# RCMX_Rev_00_BPS_NewSilk.net
KiCad netlist of a schematic drawn in EAGLE
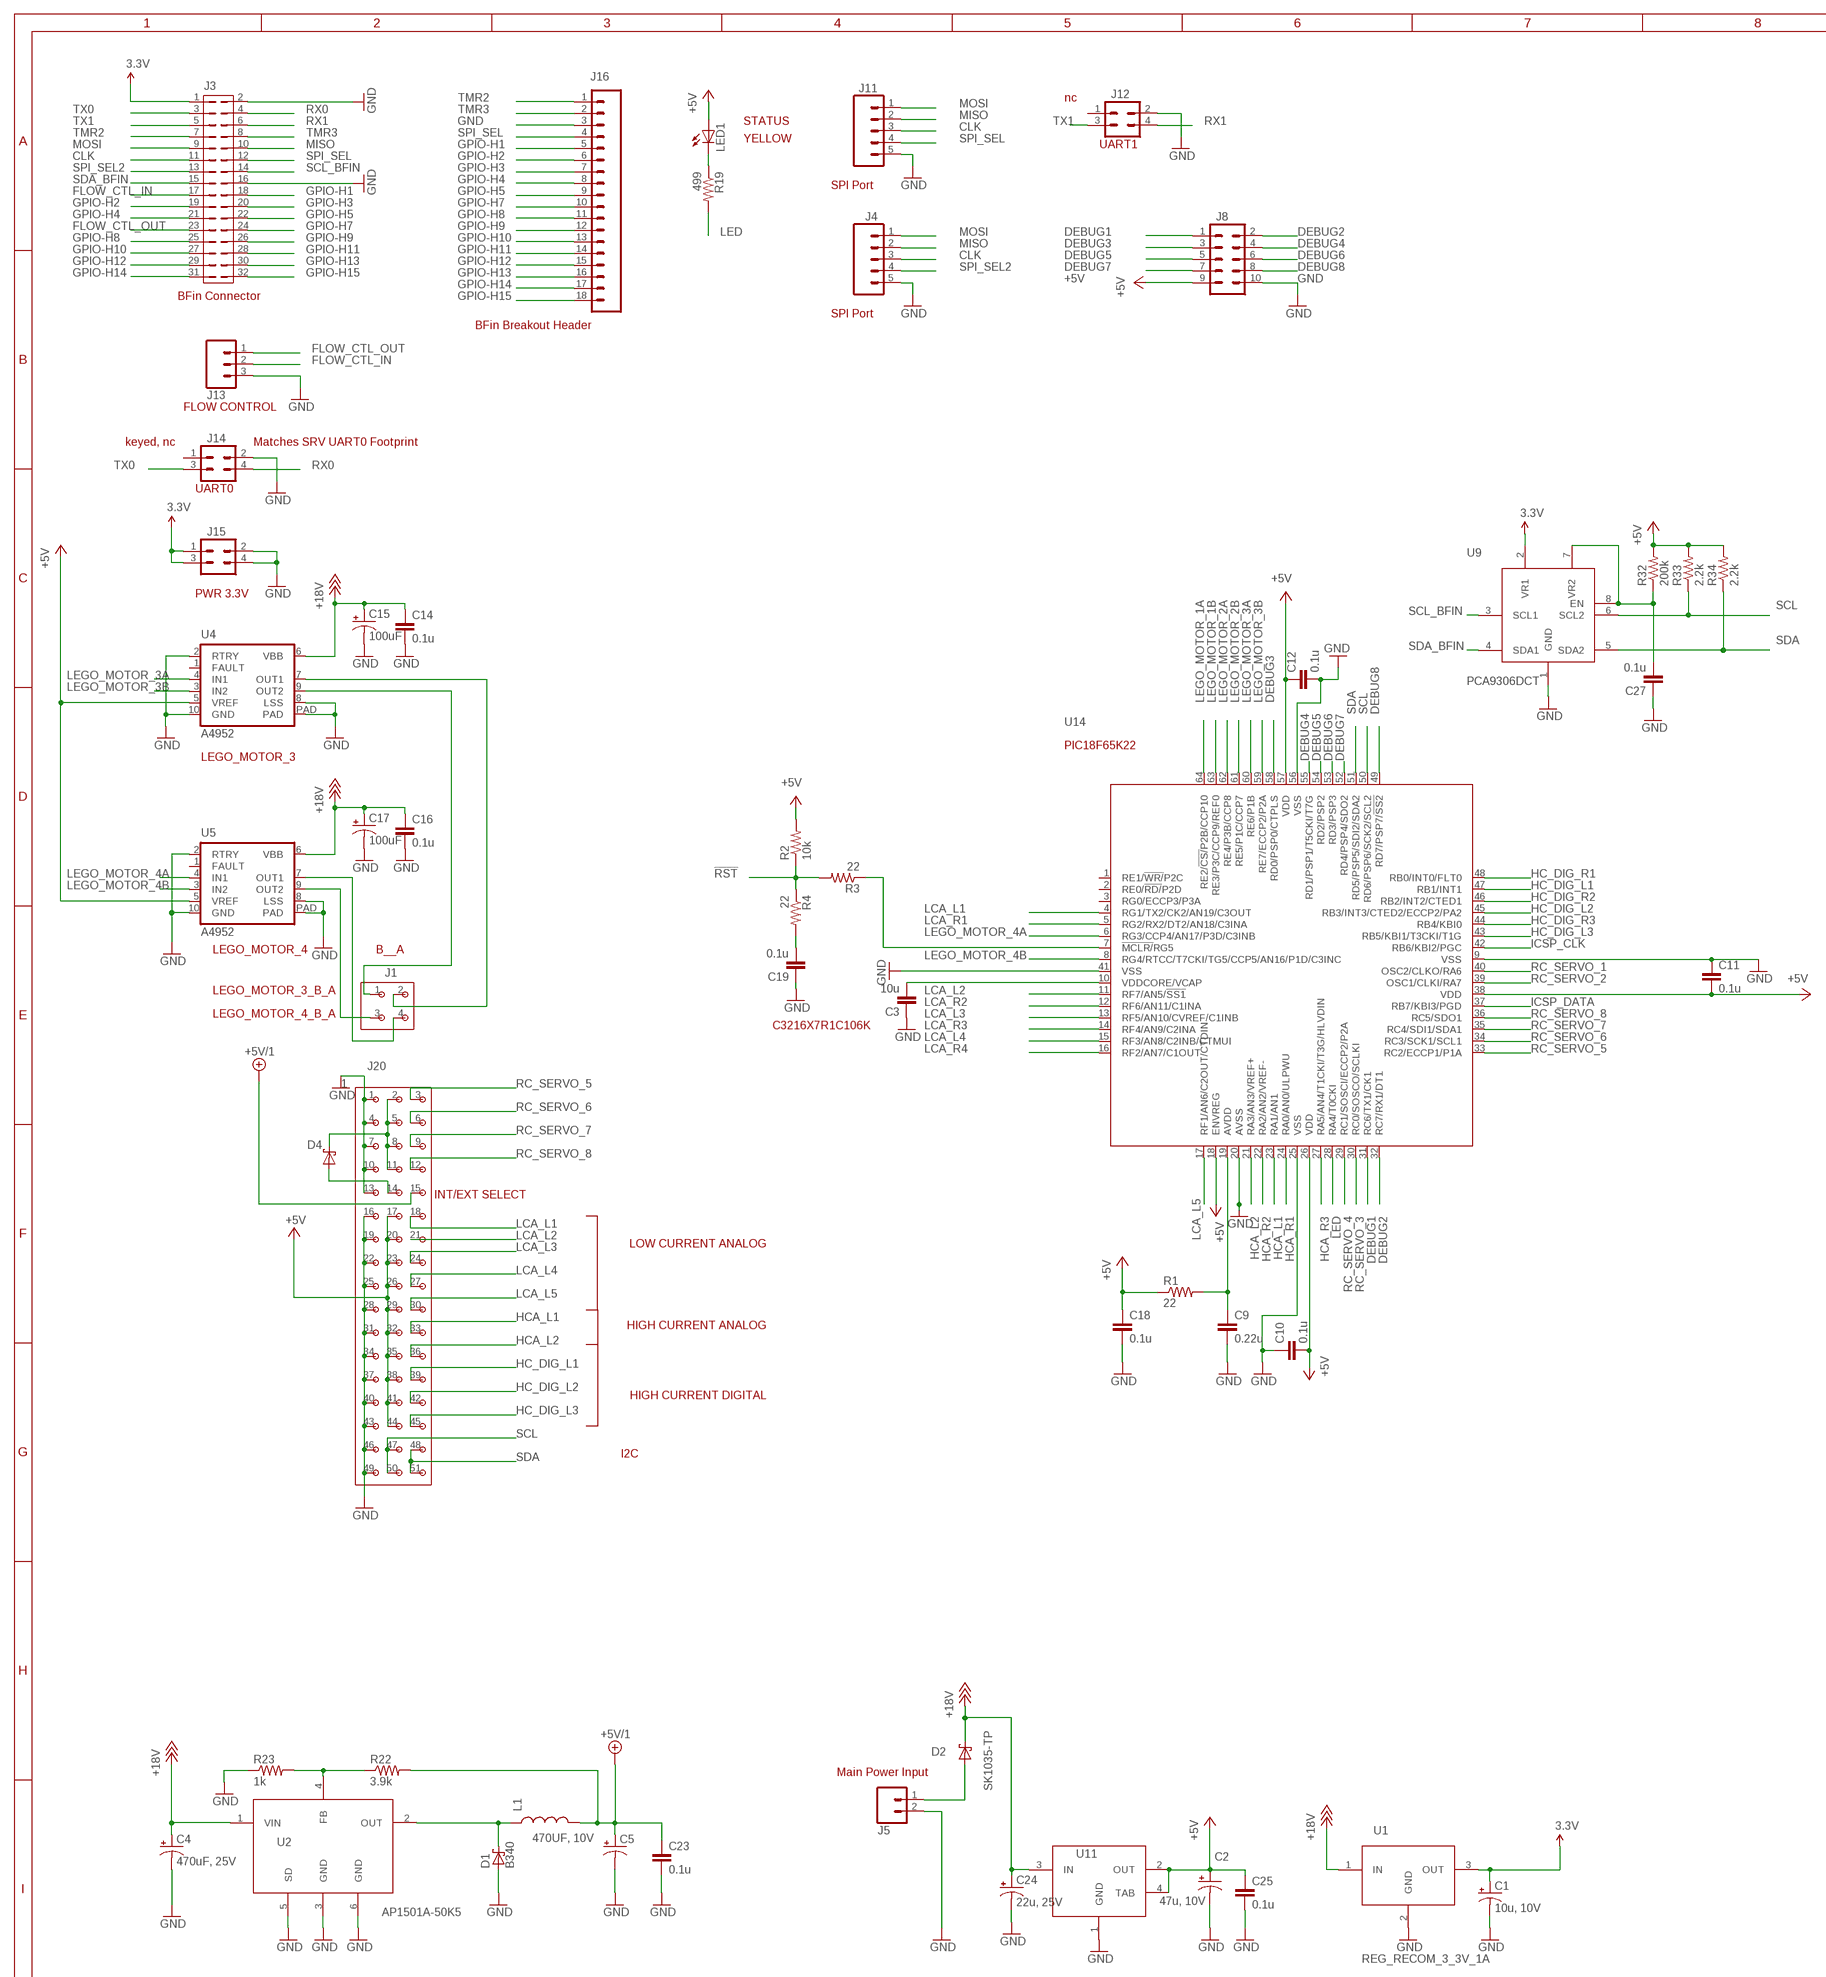
[diagram p0: schematic, sheet 1, part 1 of 2]
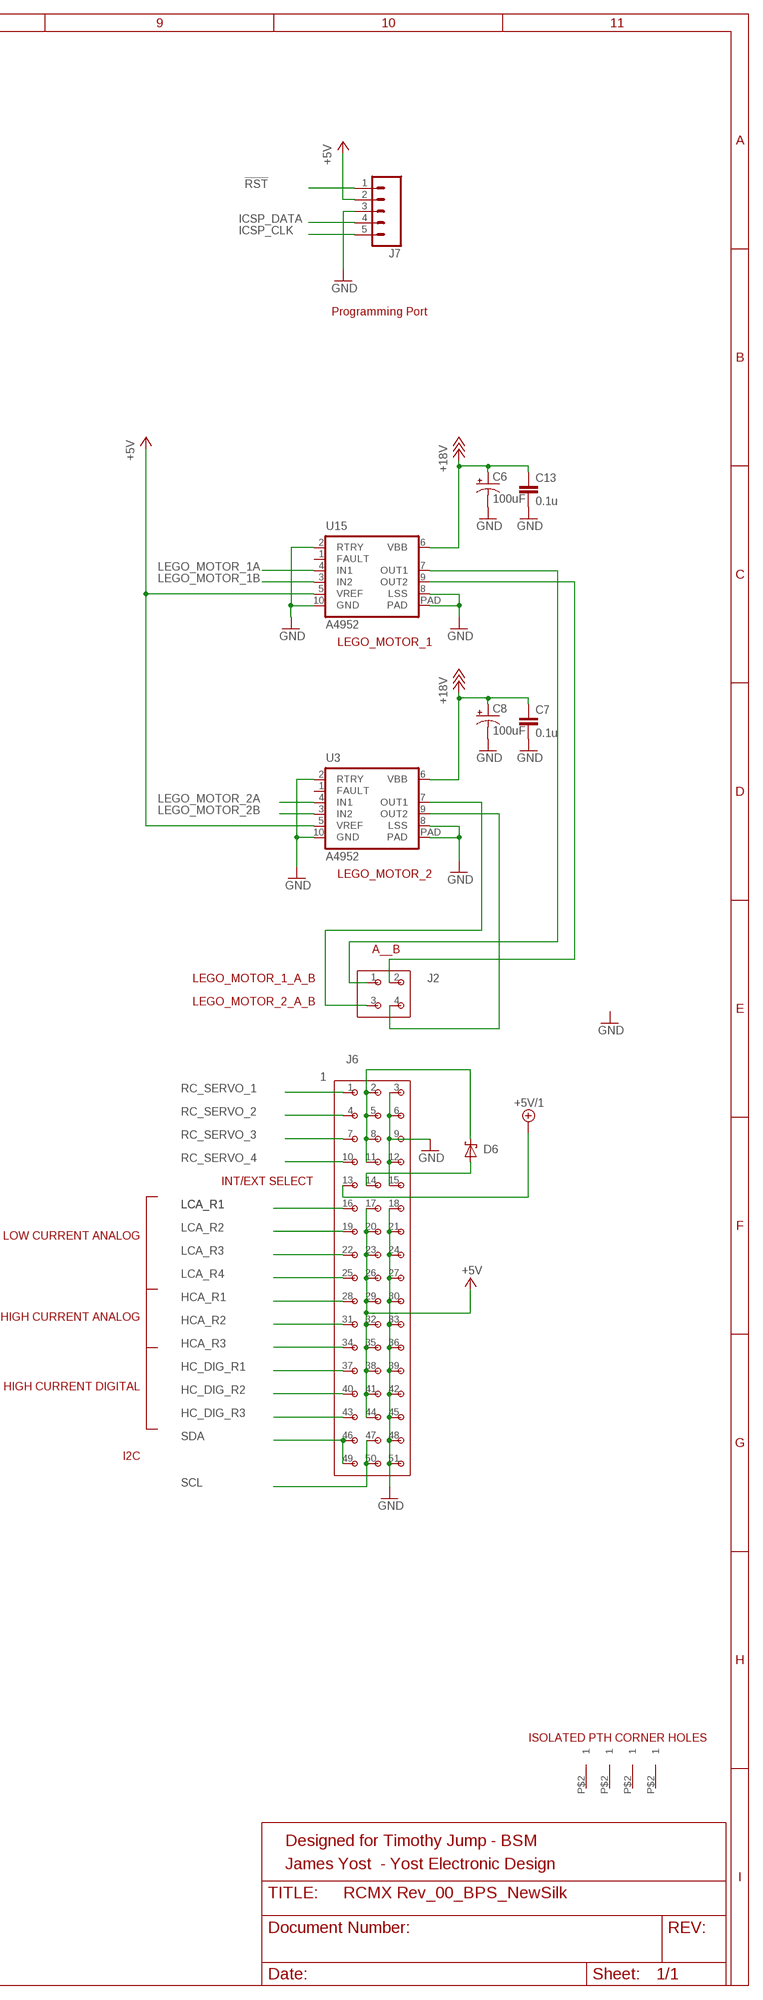
[diagram p1: schematic, sheet 1, part 2 of 2]

(export (version "E")
  (design (tool "Eeschema 10.0.6"))
  (components
    (comp (ref "C1")
      (value "10u, 10V")
      (footprint "eagle-import:EIA3216")
      (libsource (lib "eagle-import") (part "CAP_POL1206"))
    )
    (comp (ref "C2")
      (value "47u, 10V")
      (footprint "eagle-import:CAP1210_POL")
      (libsource (lib "eagle-import") (part "CAP_1210_POL"))
    )
    (comp (ref "C3")
      (value "10u")
      (footprint "eagle-import:1206")
      (libsource (lib "eagle-import") (part "CAP1206"))
    )
    (comp (ref "C4")
      (value "470uF, 25V")
      (footprint "eagle-import:PANASONIC_G")
      (libsource (lib "eagle-import") (part "CAP_POLG"))
    )
    (comp (ref "C5")
      (value "470UF, 10V")
      (footprint "eagle-import:PANASONIC_F")
      (libsource (lib "eagle-import") (part "CAP_ELT_PANASONIC_470UF"))
    )
    (comp (ref "C6")
      (value "100uF")
      (footprint "eagle-import:PANASONIC_D")
      (libsource (lib "eagle-import") (part "CAP_POLD"))
    )
    (comp (ref "C7")
      (value "0.1u")
      (footprint "eagle-import:0805")
      (libsource (lib "eagle-import") (part "CAP0805"))
    )
    (comp (ref "C8")
      (value "100uF")
      (footprint "eagle-import:PANASONIC_D")
      (libsource (lib "eagle-import") (part "CAP_POLD"))
    )
    (comp (ref "C9")
      (value "0.22u")
      (footprint "eagle-import:0805")
      (libsource (lib "eagle-import") (part "CAP0805"))
    )
    (comp (ref "C10")
      (value "0.1u")
      (footprint "eagle-import:0805")
      (libsource (lib "eagle-import") (part "CAP0805"))
    )
    (comp (ref "C11")
      (value "0.1u")
      (footprint "eagle-import:0805")
      (libsource (lib "eagle-import") (part "CAP0805"))
    )
    (comp (ref "C12")
      (value "0.1u")
      (footprint "eagle-import:0805")
      (libsource (lib "eagle-import") (part "CAP0805"))
    )
    (comp (ref "C13")
      (value "0.1u")
      (footprint "eagle-import:0805")
      (libsource (lib "eagle-import") (part "CAP0805"))
    )
    (comp (ref "C14")
      (value "0.1u")
      (footprint "eagle-import:0805")
      (libsource (lib "eagle-import") (part "CAP0805"))
    )
    (comp (ref "C15")
      (value "100uF")
      (footprint "eagle-import:PANASONIC_D")
      (libsource (lib "eagle-import") (part "CAP_POLD"))
    )
    (comp (ref "C16")
      (value "0.1u")
      (footprint "eagle-import:0805")
      (libsource (lib "eagle-import") (part "CAP0805"))
    )
    (comp (ref "C17")
      (value "100uF")
      (footprint "eagle-import:PANASONIC_D")
      (libsource (lib "eagle-import") (part "CAP_POLD"))
    )
    (comp (ref "C18")
      (value "0.1u")
      (footprint "eagle-import:0805")
      (libsource (lib "eagle-import") (part "CAP0805"))
    )
    (comp (ref "C19")
      (value "0.1u")
      (footprint "eagle-import:0805")
      (libsource (lib "eagle-import") (part "CAP0805"))
    )
    (comp (ref "C23")
      (value "0.1u")
      (footprint "eagle-import:0805")
      (libsource (lib "eagle-import") (part "CAP0805"))
    )
    (comp (ref "C24")
      (value "22u, 25V")
      (footprint "eagle-import:CAP1210_POL")
      (libsource (lib "eagle-import") (part "CAP_1210_POL"))
    )
    (comp (ref "C25")
      (value "0.1u")
      (footprint "eagle-import:0805")
      (libsource (lib "eagle-import") (part "CAP0805"))
    )
    (comp (ref "C27")
      (value "0.1u")
      (footprint "eagle-import:0805")
      (libsource (lib "eagle-import") (part "CAP0805"))
    )
    (comp (ref "D1")
      (value "B340")
      (footprint "eagle-import:SMA_DO214AC")
      (libsource (lib "eagle-import") (part "B340"))
    )
    (comp (ref "D2")
      (value "SK1035-TP")
      (footprint "eagle-import:DO214AB")
      (libsource (lib "eagle-import") (part "SK1035-TP"))
    )
    (comp (ref "D4")
      (value "SK1035-TP")
      (footprint "eagle-import:DO214AB")
      (libsource (lib "eagle-import") (part "SK1035-TP"))
    )
    (comp (ref "D6")
      (value "SK1035-TP")
      (footprint "eagle-import:DO214AB")
      (libsource (lib "eagle-import") (part "SK1035-TP"))
    )
    (comp (ref "J1")
      (value "CON_2X2_0_100")
      (footprint "eagle-import:CON_2X2_0_100")
      (libsource (lib "eagle-import") (part "CON_2X2_0_100"))
    )
    (comp (ref "J2")
      (value "CON_2X2_0_100")
      (footprint "eagle-import:CON_2X2_0_100")
      (libsource (lib "eagle-import") (part "CON_2X2_0_100"))
    )
    (comp (ref "J3")
      (value "CON_2X16_0_100")
      (footprint "eagle-import:CON_2X16_0_100")
      (libsource (lib "eagle-import") (part "CON_2X16_0_100"))
    )
    (comp (ref "J4")
      (value "M05PTH")
      (footprint "eagle-import:1X05")
      (libsource (lib "eagle-import") (part "M05PTH"))
    )
    (comp (ref "J5")
      (value "M02NG")
      (footprint "eagle-import:1X02")
      (libsource (lib "eagle-import") (part "M02NG"))
    )
    (comp (ref "J6")
      (value "CON_3X17_0_100")
      (footprint "eagle-import:CON_3X17_0_100")
      (libsource (lib "eagle-import") (part "CON_3X17_0_100"))
    )
    (comp (ref "J7")
      (value "M05PTH")
      (footprint "eagle-import:1X05")
      (libsource (lib "eagle-import") (part "SparkFun-Connectors_M05PTH"))
    )
    (comp (ref "J8")
      (value "M05X2PTH")
      (footprint "eagle-import:AVR_ICSP")
      (libsource (lib "eagle-import") (part "M05X2PTH"))
    )
    (comp (ref "J11")
      (value "M05PTH")
      (footprint "eagle-import:1X05")
      (libsource (lib "eagle-import") (part "M05PTH"))
    )
    (comp (ref "J12")
      (value "CON2X2")
      (footprint "eagle-import:CON2X2")
      (libsource (lib "eagle-import") (part "CON2X2"))
    )
    (comp (ref "J13")
      (value "M03PTH")
      (footprint "eagle-import:1X03")
      (libsource (lib "eagle-import") (part "M03PTH"))
    )
    (comp (ref "J14")
      (value "CON2X2")
      (footprint "eagle-import:CON2X2")
      (libsource (lib "eagle-import") (part "CON2X2"))
    )
    (comp (ref "J15")
      (value "CON2X2")
      (footprint "eagle-import:CON2X2")
      (libsource (lib "eagle-import") (part "CON2X2"))
    )
    (comp (ref "J16")
      (value "CON1X18")
      (footprint "eagle-import:CON1X18")
      (libsource (lib "eagle-import") (part "CON1X18"))
    )
    (comp (ref "J20")
      (value "CON_3X17_0_100")
      (footprint "eagle-import:CON_3X17_0_100")
      (libsource (lib "eagle-import") (part "CON_3X17_0_100"))
    )
    (comp (ref "L1")
      (value "IND_47UH_COILTRONICS_2_95A")
      (footprint "eagle-import:IND_PADS_SMT")
      (libsource (lib "eagle-import") (part "IND_47UH_COILTRONICS_2_95A"))
    )
    (comp (ref "LED1")
      (value "LEDCHIP-LED0805")
      (footprint "eagle-import:CHIP-LED0805")
      (libsource (lib "eagle-import") (part "LEDCHIP-LED0805"))
    )
    (comp (ref "R1")
      (value "22")
      (footprint "eagle-import:0805")
      (libsource (lib "eagle-import") (part "RESISTOR"))
    )
    (comp (ref "R2")
      (value "10k")
      (footprint "eagle-import:0805")
      (libsource (lib "eagle-import") (part "RESISTOR"))
    )
    (comp (ref "R3")
      (value "22")
      (footprint "eagle-import:0805")
      (libsource (lib "eagle-import") (part "RESISTOR"))
    )
    (comp (ref "R4")
      (value "22")
      (footprint "eagle-import:0805")
      (libsource (lib "eagle-import") (part "RESISTOR"))
    )
    (comp (ref "R19")
      (value "499")
      (footprint "eagle-import:0805")
      (libsource (lib "eagle-import") (part "RESISTOR"))
    )
    (comp (ref "R22")
      (value "3.9k")
      (footprint "eagle-import:0805")
      (libsource (lib "eagle-import") (part "RESISTOR"))
    )
    (comp (ref "R23")
      (value "1k")
      (footprint "eagle-import:0805")
      (libsource (lib "eagle-import") (part "RESISTOR"))
    )
    (comp (ref "R32")
      (value "200k")
      (footprint "eagle-import:0805")
      (libsource (lib "eagle-import") (part "RESISTOR"))
    )
    (comp (ref "R33")
      (value "2.2k")
      (footprint "eagle-import:0805")
      (libsource (lib "eagle-import") (part "RESISTOR"))
    )
    (comp (ref "R34")
      (value "2.2k")
      (footprint "eagle-import:0805")
      (libsource (lib "eagle-import") (part "RESISTOR"))
    )
    (comp (ref "U$1")
      (value "GNDPAD")
      (footprint "eagle-import:GNDPAD")
      (libsource (lib "eagle-import") (part "GNDPAD"))
    )
    (comp (ref "U$2")
      (value "GNDPAD")
      (footprint "eagle-import:GNDPAD")
      (libsource (lib "eagle-import") (part "GNDPAD"))
    )
    (comp (ref "U$7")
      (value "GNDPAD")
      (footprint "eagle-import:GNDPAD")
      (libsource (lib "eagle-import") (part "GNDPAD"))
    )
    (comp (ref "U$8")
      (value "GNDPAD")
      (footprint "eagle-import:GNDPAD")
      (libsource (lib "eagle-import") (part "GNDPAD"))
    )
    (comp (ref "U1")
      (value "REG_RECOM_3_3V_1A")
      (footprint "eagle-import:REG_RECOM_3_3V_1A")
      (libsource (lib "eagle-import") (part "REG_RECOM_3_3V_1A"))
    )
    (comp (ref "U2")
      (value "AP1501A-50K5")
      (footprint "eagle-import:TO263-5")
      (libsource (lib "eagle-import") (part "AP1501A-50K5"))
    )
    (comp (ref "U3")
      (value "A4952")
      (footprint "eagle-import:MSOP10_W_THERMAL_PAD")
      (libsource (lib "eagle-import") (part "A4952"))
    )
    (comp (ref "U4")
      (value "A4952")
      (footprint "eagle-import:MSOP10_W_THERMAL_PAD")
      (libsource (lib "eagle-import") (part "A4952"))
    )
    (comp (ref "U5")
      (value "A4952")
      (footprint "eagle-import:MSOP10_W_THERMAL_PAD")
      (libsource (lib "eagle-import") (part "A4952"))
    )
    (comp (ref "U9")
      (value "PCA9306DCT")
      (footprint "eagle-import:TEST08")
      (libsource (lib "eagle-import") (part "PCA9306DCT"))
    )
    (comp (ref "U11")
      (value "TLV1117-5")
      (footprint "eagle-import:SOT223")
      (libsource (lib "eagle-import") (part "TLV1117-5"))
    )
    (comp (ref "U14")
      (value "MICRO_C_PIC18F65K22")
      (footprint "eagle-import:64PIN_TQFP_10X10X1MM")
      (libsource (lib "eagle-import") (part "MICRO_C_PIC18F65K22"))
    )
    (comp (ref "U15")
      (value "A4952")
      (footprint "eagle-import:MSOP10_W_THERMAL_PAD")
      (libsource (lib "eagle-import") (part "A4952"))
    )
  )
  (nets
    (net (code "1") (name "+5V") (class "Default")
      (node (ref "C10") (pin "2") (pinfunction "2_2") (pintype "passive"))
      (node (ref "C11") (pin "2") (pinfunction "2_2") (pintype "passive"))
      (node (ref "C12") (pin "1") (pinfunction "1_1") (pintype "passive"))
      (node (ref "C18") (pin "1") (pinfunction "1_1") (pintype "passive"))
      (node (ref "C2") (pin "1") (pinfunction "+_1") (pintype "passive"))
      (node (ref "C25") (pin "1") (pinfunction "1_1") (pintype "passive"))
      (node (ref "J20") (pin "17") (pinfunction "17_17") (pintype "passive"))
      (node (ref "J20") (pin "20") (pinfunction "20_20") (pintype "passive"))
      (node (ref "J20") (pin "23") (pinfunction "23_23") (pintype "passive"))
      (node (ref "J20") (pin "26") (pinfunction "26_26") (pintype "passive"))
      (node (ref "J20") (pin "29") (pinfunction "29_29") (pintype "passive"))
      (node (ref "J20") (pin "32") (pinfunction "32_32") (pintype "passive"))
      (node (ref "J20") (pin "35") (pinfunction "35_35") (pintype "passive"))
      (node (ref "J20") (pin "38") (pinfunction "38_38") (pintype "passive"))
      (node (ref "J20") (pin "41") (pinfunction "41_41") (pintype "passive"))
      (node (ref "J20") (pin "44") (pinfunction "44_44") (pintype "passive"))
      (node (ref "J6") (pin "17") (pinfunction "17_17") (pintype "passive"))
      (node (ref "J6") (pin "20") (pinfunction "20_20") (pintype "passive"))
      (node (ref "J6") (pin "23") (pinfunction "23_23") (pintype "passive"))
      (node (ref "J6") (pin "26") (pinfunction "26_26") (pintype "passive"))
      (node (ref "J6") (pin "29") (pinfunction "29_29") (pintype "passive"))
      (node (ref "J6") (pin "32") (pinfunction "32_32") (pintype "passive"))
      (node (ref "J6") (pin "35") (pinfunction "35_35") (pintype "passive"))
      (node (ref "J6") (pin "38") (pinfunction "38_38") (pintype "passive"))
      (node (ref "J6") (pin "41") (pinfunction "41_41") (pintype "passive"))
      (node (ref "J6") (pin "44") (pinfunction "44_44") (pintype "passive"))
      (node (ref "J7") (pin "2") (pinfunction "2_2") (pintype "passive"))
      (node (ref "J8") (pin "9") (pinfunction "9_9") (pintype "passive"))
      (node (ref "LED1") (pin "A") (pinfunction "A_A") (pintype "passive"))
      (node (ref "R1") (pin "1") (pinfunction "1_1") (pintype "passive"))
      (node (ref "R2") (pin "2") (pinfunction "2_2") (pintype "passive"))
      (node (ref "R32") (pin "2") (pinfunction "2_2") (pintype "passive"))
      (node (ref "R33") (pin "2") (pinfunction "2_2") (pintype "passive"))
      (node (ref "R34") (pin "2") (pinfunction "2_2") (pintype "passive"))
      (node (ref "U11") (pin "2") (pinfunction "OUT_2") (pintype "bidirectional"))
      (node (ref "U11") (pin "4") (pinfunction "TAB_4") (pintype "bidirectional"))
      (node (ref "U14") (pin "18") (pinfunction "ENVREG_18") (pintype "input"))
      (node (ref "U14") (pin "26") (pinfunction "VDD_26") (pintype "power_in"))
      (node (ref "U14") (pin "38") (pinfunction "VDD_38") (pintype "power_in"))
      (node (ref "U14") (pin "57") (pinfunction "VDD_57") (pintype "power_in"))
      (node (ref "U15") (pin "5") (pinfunction "VREF_5") (pintype "passive"))
      (node (ref "U3") (pin "5") (pinfunction "VREF_5") (pintype "passive"))
      (node (ref "U4") (pin "5") (pinfunction "VREF_5") (pintype "passive"))
      (node (ref "U5") (pin "5") (pinfunction "VREF_5") (pintype "passive"))
    )
    (net (code "2") (name "+5V{slash}1") (class "Default")
      (node (ref "C23") (pin "1") (pinfunction "1_1") (pintype "passive"))
      (node (ref "C5") (pin "+") (pinfunction "+_+") (pintype "passive"))
      (node (ref "J20") (pin "15") (pinfunction "15_15") (pintype "passive"))
      (node (ref "J6") (pin "13") (pinfunction "13_13") (pintype "passive"))
      (node (ref "L1") (pin "2") (pinfunction "2_2") (pintype "passive"))
      (node (ref "R22") (pin "2") (pinfunction "2_2") (pintype "passive"))
    )
    (net (code "3") (name "+18V") (class "Default")
      (node (ref "C13") (pin "1") (pinfunction "1_1") (pintype "passive"))
      (node (ref "C14") (pin "1") (pinfunction "1_1") (pintype "passive"))
      (node (ref "C15") (pin "+") (pinfunction "+_+") (pintype "passive"))
      (node (ref "C16") (pin "1") (pinfunction "1_1") (pintype "passive"))
      (node (ref "C17") (pin "+") (pinfunction "+_+") (pintype "passive"))
      (node (ref "C24") (pin "1") (pinfunction "+_1") (pintype "passive"))
      (node (ref "C4") (pin "+") (pinfunction "+_+") (pintype "passive"))
      (node (ref "C6") (pin "+") (pinfunction "+_+") (pintype "passive"))
      (node (ref "C7") (pin "1") (pinfunction "1_1") (pintype "passive"))
      (node (ref "C8") (pin "+") (pinfunction "+_+") (pintype "passive"))
      (node (ref "D2") (pin "1") (pinfunction "C_1") (pintype "passive"))
      (node (ref "U1") (pin "1") (pinfunction "IN_1") (pintype "bidirectional"))
      (node (ref "U11") (pin "3") (pinfunction "IN_3") (pintype "bidirectional"))
      (node (ref "U15") (pin "6") (pinfunction "VBB_6") (pintype "input"))
      (node (ref "U2") (pin "1") (pinfunction "VIN_1") (pintype "bidirectional"))
      (node (ref "U3") (pin "6") (pinfunction "VBB_6") (pintype "input"))
      (node (ref "U4") (pin "6") (pinfunction "VBB_6") (pintype "input"))
      (node (ref "U5") (pin "6") (pinfunction "VBB_6") (pintype "input"))
    )
    (net (code "4") (name "/CLK") (class "Default")
      (node (ref "J11") (pin "3") (pinfunction "3_3") (pintype "passive"))
      (node (ref "J3") (pin "11") (pinfunction "11_11") (pintype "passive"))
      (node (ref "J4") (pin "3") (pinfunction "3_3") (pintype "passive"))
    )
    (net (code "5") (name "/DEBUG1") (class "Default")
      (node (ref "J8") (pin "1") (pinfunction "1_1") (pintype "passive"))
      (node (ref "U14") (pin "31") (pinfunction "RC6/TX1/CK1_31") (pintype "bidirectional"))
    )
    (net (code "6") (name "/DEBUG2") (class "Default")
      (node (ref "J8") (pin "2") (pinfunction "2_2") (pintype "passive"))
      (node (ref "U14") (pin "32") (pinfunction "RC7/RX1/DT1_32") (pintype "bidirectional"))
    )
    (net (code "7") (name "/DEBUG3") (class "Default")
      (node (ref "J8") (pin "3") (pinfunction "3_3") (pintype "passive"))
      (node (ref "U14") (pin "58") (pinfunction "RD0/PSP0/CTPLS_58") (pintype "bidirectional"))
    )
    (net (code "8") (name "/DEBUG4") (class "Default")
      (node (ref "J8") (pin "4") (pinfunction "4_4") (pintype "passive"))
      (node (ref "U14") (pin "55") (pinfunction "RD1/PSP1/T5CKI/T7G_55") (pintype "bidirectional"))
    )
    (net (code "9") (name "/DEBUG5") (class "Default")
      (node (ref "J8") (pin "5") (pinfunction "5_5") (pintype "passive"))
      (node (ref "U14") (pin "54") (pinfunction "RD2/PSP2_54") (pintype "bidirectional"))
    )
    (net (code "10") (name "/DEBUG6") (class "Default")
      (node (ref "J8") (pin "6") (pinfunction "6_6") (pintype "passive"))
      (node (ref "U14") (pin "53") (pinfunction "RD3/PSP3_53") (pintype "bidirectional"))
    )
    (net (code "11") (name "/DEBUG7") (class "Default")
      (node (ref "J8") (pin "7") (pinfunction "7_7") (pintype "passive"))
      (node (ref "U14") (pin "52") (pinfunction "RD4/PSP4/SDO2_52") (pintype "bidirectional"))
    )
    (net (code "12") (name "/DEBUG8") (class "Default")
      (node (ref "J8") (pin "8") (pinfunction "8_8") (pintype "passive"))
      (node (ref "U14") (pin "49") (pinfunction "RD7/PSP7/~{SS2}_49") (pintype "bidirectional"))
    )
    (net (code "13") (name "/FLOW_CTL_IN") (class "Default")
      (node (ref "J13") (pin "2") (pinfunction "2_2") (pintype "passive"))
      (node (ref "J3") (pin "17") (pinfunction "17_17") (pintype "passive"))
    )
    (net (code "14") (name "/FLOW_CTL_OUT") (class "Default")
      (node (ref "J13") (pin "1") (pinfunction "1_1") (pintype "passive"))
      (node (ref "J3") (pin "23") (pinfunction "23_23") (pintype "passive"))
    )
    (net (code "15") (name "/GPIO-H1") (class "Default")
      (node (ref "J16") (pin "5") (pinfunction "5_5") (pintype "passive"))
      (node (ref "J3") (pin "18") (pinfunction "18_18") (pintype "passive"))
    )
    (net (code "16") (name "/GPIO-H2") (class "Default")
      (node (ref "J16") (pin "6") (pinfunction "6_6") (pintype "passive"))
      (node (ref "J3") (pin "19") (pinfunction "19_19") (pintype "passive"))
    )
    (net (code "17") (name "/GPIO-H3") (class "Default")
      (node (ref "J16") (pin "7") (pinfunction "7_7") (pintype "passive"))
      (node (ref "J3") (pin "20") (pinfunction "20_20") (pintype "passive"))
    )
    (net (code "18") (name "/GPIO-H4") (class "Default")
      (node (ref "J16") (pin "8") (pinfunction "8_8") (pintype "passive"))
      (node (ref "J3") (pin "21") (pinfunction "21_21") (pintype "passive"))
    )
    (net (code "19") (name "/GPIO-H5") (class "Default")
      (node (ref "J16") (pin "9") (pinfunction "9_9") (pintype "passive"))
      (node (ref "J3") (pin "22") (pinfunction "22_22") (pintype "passive"))
    )
    (net (code "20") (name "/GPIO-H7") (class "Default")
      (node (ref "J16") (pin "10") (pinfunction "10_10") (pintype "passive"))
      (node (ref "J3") (pin "24") (pinfunction "24_24") (pintype "passive"))
    )
    (net (code "21") (name "/GPIO-H8") (class "Default")
      (node (ref "J16") (pin "11") (pinfunction "11_11") (pintype "passive"))
      (node (ref "J3") (pin "25") (pinfunction "25_25") (pintype "passive"))
    )
    (net (code "22") (name "/GPIO-H9") (class "Default")
      (node (ref "J16") (pin "12") (pinfunction "12_12") (pintype "passive"))
      (node (ref "J3") (pin "26") (pinfunction "26_26") (pintype "passive"))
    )
    (net (code "23") (name "/GPIO-H10") (class "Default")
      (node (ref "J16") (pin "13") (pinfunction "13_13") (pintype "passive"))
      (node (ref "J3") (pin "27") (pinfunction "27_27") (pintype "passive"))
    )
    (net (code "24") (name "/GPIO-H11") (class "Default")
      (node (ref "J16") (pin "14") (pinfunction "14_14") (pintype "passive"))
      (node (ref "J3") (pin "28") (pinfunction "28_28") (pintype "passive"))
    )
    (net (code "25") (name "/GPIO-H12") (class "Default")
      (node (ref "J16") (pin "15") (pinfunction "15_15") (pintype "passive"))
      (node (ref "J3") (pin "29") (pinfunction "29_29") (pintype "passive"))
    )
    (net (code "26") (name "/GPIO-H13") (class "Default")
      (node (ref "J16") (pin "16") (pinfunction "16_16") (pintype "passive"))
      (node (ref "J3") (pin "30") (pinfunction "30_30") (pintype "passive"))
    )
    (net (code "27") (name "/GPIO-H14") (class "Default")
      (node (ref "J16") (pin "17") (pinfunction "17_17") (pintype "passive"))
      (node (ref "J3") (pin "31") (pinfunction "31_31") (pintype "passive"))
    )
    (net (code "28") (name "/GPIO-H15") (class "Default")
      (node (ref "J16") (pin "18") (pinfunction "18_18") (pintype "passive"))
      (node (ref "J3") (pin "32") (pinfunction "32_32") (pintype "passive"))
    )
    (net (code "29") (name "/HCA_L1") (class "Default")
      (node (ref "J20") (pin "33") (pinfunction "33_33") (pintype "passive"))
      (node (ref "U14") (pin "23") (pinfunction "RA1/AN1_23") (pintype "bidirectional"))
    )
    (net (code "30") (name "/HCA_L2") (class "Default")
      (node (ref "J20") (pin "36") (pinfunction "36_36") (pintype "passive"))
      (node (ref "U14") (pin "21") (pinfunction "RA3/AN3/VREF+_21") (pintype "bidirectional"))
    )
    (net (code "31") (name "/HCA_R1") (class "Default")
      (node (ref "J6") (pin "28") (pinfunction "28_28") (pintype "passive"))
      (node (ref "U14") (pin "24") (pinfunction "RA0/AN0/ULPWU_24") (pintype "bidirectional"))
    )
    (net (code "32") (name "/HCA_R2") (class "Default")
      (node (ref "J6") (pin "31") (pinfunction "31_31") (pintype "passive"))
      (node (ref "U14") (pin "22") (pinfunction "RA2/AN2/VREF-_22") (pintype "bidirectional"))
    )
    (net (code "33") (name "/HCA_R3") (class "Default")
      (node (ref "J6") (pin "34") (pinfunction "34_34") (pintype "passive"))
      (node (ref "U14") (pin "27") (pinfunction "RA5/AN4/T1CKI/T3G/HLVDIN_27") (pintype "bidirectional"))
    )
    (net (code "34") (name "/HC_DIG_L1") (class "Default")
      (node (ref "J20") (pin "39") (pinfunction "39_39") (pintype "passive"))
      (node (ref "U14") (pin "47") (pinfunction "RB1/INT1_47") (pintype "bidirectional"))
    )
    (net (code "35") (name "/HC_DIG_L2") (class "Default")
      (node (ref "J20") (pin "42") (pinfunction "42_42") (pintype "passive"))
      (node (ref "U14") (pin "45") (pinfunction "RB3/INT3/CTED2/ECCP2/PA2_45") (pintype "bidirectional"))
    )
    (net (code "36") (name "/HC_DIG_L3") (class "Default")
      (node (ref "J20") (pin "45") (pinfunction "45_45") (pintype "passive"))
      (node (ref "U14") (pin "43") (pinfunction "RB5/KBI1/T3CKI/T1G_43") (pintype "bidirectional"))
    )
    (net (code "37") (name "/HC_DIG_R1") (class "Default")
      (node (ref "J6") (pin "37") (pinfunction "37_37") (pintype "passive"))
      (node (ref "U14") (pin "48") (pinfunction "RB0/INT0/FLT0_48") (pintype "bidirectional"))
    )
    (net (code "38") (name "/HC_DIG_R2") (class "Default")
      (node (ref "J6") (pin "40") (pinfunction "40_40") (pintype "passive"))
      (node (ref "U14") (pin "46") (pinfunction "RB2/INT2/CTED1_46") (pintype "bidirectional"))
    )
    (net (code "39") (name "/HC_DIG_R3") (class "Default")
      (node (ref "J6") (pin "43") (pinfunction "43_43") (pintype "passive"))
      (node (ref "U14") (pin "44") (pinfunction "RB4/KBI0_44") (pintype "bidirectional"))
    )
    (net (code "40") (name "/ICSP_CLK") (class "Default")
      (node (ref "J7") (pin "5") (pinfunction "5_5") (pintype "passive"))
      (node (ref "U14") (pin "42") (pinfunction "RB6/KBI2/PGC_42") (pintype "bidirectional"))
    )
    (net (code "41") (name "/ICSP_DATA") (class "Default")
      (node (ref "J7") (pin "4") (pinfunction "4_4") (pintype "passive"))
      (node (ref "U14") (pin "37") (pinfunction "RB7/KBI3/PGD_37") (pintype "bidirectional"))
    )
    (net (code "42") (name "/LCA_L1") (class "Default")
      (node (ref "J20") (pin "18") (pinfunction "18_18") (pintype "passive"))
      (node (ref "U14") (pin "4") (pinfunction "RG1/TX2/CK2/AN19/C3OUT_4") (pintype "bidirectional"))
    )
    (net (code "43") (name "/LCA_L2") (class "Default")
      (node (ref "J20") (pin "21") (pinfunction "21_21") (pintype "passive"))
      (node (ref "U14") (pin "11") (pinfunction "RF7/AN5/~{SS1}_11") (pintype "bidirectional"))
    )
    (net (code "44") (name "/LCA_L3") (class "Default")
      (node (ref "J20") (pin "24") (pinfunction "24_24") (pintype "passive"))
      (node (ref "U14") (pin "13") (pinfunction "RF5/AN10/CVREF/C1INB_13") (pintype "bidirectional"))
    )
    (net (code "45") (name "/LCA_L4") (class "Default")
      (node (ref "J20") (pin "27") (pinfunction "27_27") (pintype "passive"))
      (node (ref "U14") (pin "15") (pinfunction "RF3/AN8/C2INB/CTMUI_15") (pintype "bidirectional"))
    )
    (net (code "46") (name "/LCA_L5") (class "Default")
      (node (ref "J20") (pin "30") (pinfunction "30_30") (pintype "passive"))
      (node (ref "U14") (pin "17") (pinfunction "RF1/AN6/C2OUT/CTDIN_17") (pintype "bidirectional"))
    )
    (net (code "47") (name "/LCA_R1") (class "Default")
      (node (ref "J6") (pin "16") (pinfunction "16_16") (pintype "passive"))
      (node (ref "U14") (pin "5") (pinfunction "RG2/RX2/DT2/AN18/C3INA_5") (pintype "bidirectional"))
    )
    (net (code "48") (name "/LCA_R2") (class "Default")
      (node (ref "J6") (pin "19") (pinfunction "19_19") (pintype "passive"))
      (node (ref "U14") (pin "12") (pinfunction "RF6/AN11/C1INA_12") (pintype "bidirectional"))
    )
    (net (code "49") (name "/LCA_R3") (class "Default")
      (node (ref "J6") (pin "22") (pinfunction "22_22") (pintype "passive"))
      (node (ref "U14") (pin "14") (pinfunction "RF4/AN9/C2INA_14") (pintype "bidirectional"))
    )
    (net (code "50") (name "/LCA_R4") (class "Default")
      (node (ref "J6") (pin "25") (pinfunction "25_25") (pintype "passive"))
      (node (ref "U14") (pin "16") (pinfunction "RF2/AN7/C1OUT_16") (pintype "bidirectional"))
    )
    (net (code "51") (name "/LED") (class "Default")
      (node (ref "R19") (pin "2") (pinfunction "2_2") (pintype "passive"))
      (node (ref "U14") (pin "28") (pinfunction "RA4/T0CKI_28") (pintype "bidirectional"))
    )
    (net (code "52") (name "/LEGO_MOTOR_1A") (class "Default")
      (node (ref "U14") (pin "64") (pinfunction "RE2/~{CS/}P2B/CCP10_64") (pintype "bidirectional"))
      (node (ref "U15") (pin "4") (pinfunction "IN1_4") (pintype "input"))
    )
    (net (code "53") (name "/LEGO_MOTOR_1B") (class "Default")
      (node (ref "U14") (pin "63") (pinfunction "RE3/P3C/CCP9/REF0_63") (pintype "bidirectional"))
      (node (ref "U15") (pin "3") (pinfunction "IN2_3") (pintype "input"))
    )
    (net (code "54") (name "/LEGO_MOTOR_2A") (class "Default")
      (node (ref "U14") (pin "62") (pinfunction "RE4/P3B/CCP8_62") (pintype "bidirectional"))
      (node (ref "U3") (pin "4") (pinfunction "IN1_4") (pintype "input"))
    )
    (net (code "55") (name "/LEGO_MOTOR_2B") (class "Default")
      (node (ref "U14") (pin "61") (pinfunction "RE5/P1C/CCP7_61") (pintype "bidirectional"))
      (node (ref "U3") (pin "3") (pinfunction "IN2_3") (pintype "input"))
    )
    (net (code "56") (name "/LEGO_MOTOR_3A") (class "Default")
      (node (ref "U14") (pin "60") (pinfunction "RE6/P1B_60") (pintype "bidirectional"))
      (node (ref "U4") (pin "4") (pinfunction "IN1_4") (pintype "input"))
    )
    (net (code "57") (name "/LEGO_MOTOR_3B") (class "Default")
      (node (ref "U14") (pin "59") (pinfunction "RE7/ECCP2/P2A_59") (pintype "bidirectional"))
      (node (ref "U4") (pin "3") (pinfunction "IN2_3") (pintype "input"))
    )
    (net (code "58") (name "/LEGO_MOTOR_4A") (class "Default")
      (node (ref "U14") (pin "6") (pinfunction "RG3/CCP4/AN17/P3D/C3INB_6") (pintype "bidirectional"))
      (node (ref "U5") (pin "4") (pinfunction "IN1_4") (pintype "input"))
    )
    (net (code "59") (name "/LEGO_MOTOR_4B") (class "Default")
      (node (ref "U14") (pin "8") (pinfunction "RG4/RTCC/T7CKI/TG5/CCP5/AN16/P1D/C3INC_8") (pintype "bidirectional"))
      (node (ref "U5") (pin "3") (pinfunction "IN2_3") (pintype "input"))
    )
    (net (code "60") (name "/MISO") (class "Default")
      (node (ref "J11") (pin "2") (pinfunction "2_2") (pintype "passive"))
      (node (ref "J3") (pin "10") (pinfunction "10_10") (pintype "passive"))
      (node (ref "J4") (pin "2") (pinfunction "2_2") (pintype "passive"))
    )
    (net (code "61") (name "/MOSI") (class "Default")
      (node (ref "J11") (pin "1") (pinfunction "1_1") (pintype "passive"))
      (node (ref "J3") (pin "9") (pinfunction "9_9") (pintype "passive"))
      (node (ref "J4") (pin "1") (pinfunction "1_1") (pintype "passive"))
    )
    (net (code "62") (name "/RC_SERVO_1") (class "Default")
      (node (ref "J6") (pin "1") (pinfunction "1_1") (pintype "passive"))
      (node (ref "U14") (pin "40") (pinfunction "OSC2/CLKO/RA6_40") (pintype "output"))
    )
    (net (code "63") (name "/RC_SERVO_2") (class "Default")
      (node (ref "J6") (pin "4") (pinfunction "4_4") (pintype "passive"))
      (node (ref "U14") (pin "39") (pinfunction "OSC1/CLKI/RA7_39") (pintype "input"))
    )
    (net (code "64") (name "/RC_SERVO_3") (class "Default")
      (node (ref "J6") (pin "7") (pinfunction "7_7") (pintype "passive"))
      (node (ref "U14") (pin "30") (pinfunction "RC0/SOSCO/SCLKI_30") (pintype "bidirectional"))
    )
    (net (code "65") (name "/RC_SERVO_4") (class "Default")
      (node (ref "J6") (pin "10") (pinfunction "10_10") (pintype "passive"))
      (node (ref "U14") (pin "29") (pinfunction "RC1/SOSCI/ECCP2/P2A_29") (pintype "bidirectional"))
    )
    (net (code "66") (name "/RC_SERVO_5") (class "Default")
      (node (ref "J20") (pin "3") (pinfunction "3_3") (pintype "passive"))
      (node (ref "U14") (pin "33") (pinfunction "RC2/ECCP1/P1A_33") (pintype "bidirectional"))
    )
    (net (code "67") (name "/RC_SERVO_6") (class "Default")
      (node (ref "J20") (pin "6") (pinfunction "6_6") (pintype "passive"))
      (node (ref "U14") (pin "34") (pinfunction "RC3/SCK1/SCL1_34") (pintype "bidirectional"))
    )
    (net (code "68") (name "/RC_SERVO_7") (class "Default")
      (node (ref "J20") (pin "9") (pinfunction "9_9") (pintype "passive"))
      (node (ref "U14") (pin "35") (pinfunction "RC4/SDI1/SDA1_35") (pintype "bidirectional"))
    )
    (net (code "69") (name "/RC_SERVO_8") (class "Default")
      (node (ref "J20") (pin "12") (pinfunction "12_12") (pintype "passive"))
      (node (ref "U14") (pin "36") (pinfunction "RC5/SDO1_36") (pintype "bidirectional"))
    )
    (net (code "70") (name "/RX0") (class "Default")
      (node (ref "J14") (pin "4") (pinfunction "4_4") (pintype "passive"))
      (node (ref "J3") (pin "4") (pinfunction "4_4") (pintype "passive"))
    )
    (net (code "71") (name "/RX1") (class "Default")
      (node (ref "J12") (pin "4") (pinfunction "4_4") (pintype "passive"))
      (node (ref "J3") (pin "6") (pinfunction "6_6") (pintype "passive"))
    )
    (net (code "72") (name "/SCL") (class "Default")
      (node (ref "J20") (pin "47") (pinfunction "47_47") (pintype "passive"))
      (node (ref "J20") (pin "50") (pinfunction "50_50") (pintype "passive"))
      (node (ref "J6") (pin "47") (pinfunction "47_47") (pintype "passive"))
      (node (ref "J6") (pin "50") (pinfunction "50_50") (pintype "passive"))
      (node (ref "R33") (pin "1") (pinfunction "1_1") (pintype "passive"))
      (node (ref "U14") (pin "50") (pinfunction "RD6/PSP6/SCK2/SCL2_50") (pintype "bidirectional"))
      (node (ref "U9") (pin "6") (pinfunction "SCL2_6") (pintype "bidirectional"))
    )
    (net (code "73") (name "/SCL_BFIN") (class "Default")
      (node (ref "J3") (pin "14") (pinfunction "14_14") (pintype "passive"))
      (node (ref "U9") (pin "3") (pinfunction "SCL1_3") (pintype "bidirectional"))
    )
    (net (code "74") (name "/SDA") (class "Default")
      (node (ref "J20") (pin "48") (pinfunction "48_48") (pintype "passive"))
      (node (ref "J20") (pin "51") (pinfunction "51_51") (pintype "passive"))
      (node (ref "J6") (pin "46") (pinfunction "46_46") (pintype "passive"))
      (node (ref "J6") (pin "49") (pinfunction "49_49") (pintype "passive"))
      (node (ref "R34") (pin "1") (pinfunction "1_1") (pintype "passive"))
      (node (ref "U14") (pin "51") (pinfunction "RD5/PSP5/SDI2/SDA2_51") (pintype "bidirectional"))
      (node (ref "U9") (pin "5") (pinfunction "SDA2_5") (pintype "bidirectional"))
    )
    (net (code "75") (name "/SDA_BFIN") (class "Default")
      (node (ref "J3") (pin "15") (pinfunction "15_15") (pintype "passive"))
      (node (ref "U9") (pin "4") (pinfunction "SDA1_4") (pintype "bidirectional"))
    )
    (net (code "76") (name "/SPI_SEL") (class "Default")
      (node (ref "J11") (pin "4") (pinfunction "4_4") (pintype "passive"))
      (node (ref "J16") (pin "4") (pinfunction "4_4") (pintype "passive"))
      (node (ref "J3") (pin "12") (pinfunction "12_12") (pintype "passive"))
    )
    (net (code "77") (name "/SPI_SEL2") (class "Default")
      (node (ref "J3") (pin "13") (pinfunction "13_13") (pintype "passive"))
      (node (ref "J4") (pin "4") (pinfunction "4_4") (pintype "passive"))
    )
    (net (code "78") (name "/TMR2") (class "Default")
      (node (ref "J16") (pin "1") (pinfunction "1_1") (pintype "passive"))
      (node (ref "J3") (pin "7") (pinfunction "7_7") (pintype "passive"))
    )
    (net (code "79") (name "/TMR3") (class "Default")
      (node (ref "J16") (pin "2") (pinfunction "2_2") (pintype "passive"))
      (node (ref "J3") (pin "8") (pinfunction "8_8") (pintype "passive"))
    )
    (net (code "80") (name "/TX0") (class "Default")
      (node (ref "J14") (pin "3") (pinfunction "3_3") (pintype "passive"))
      (node (ref "J3") (pin "3") (pinfunction "3_3") (pintype "passive"))
    )
    (net (code "81") (name "/TX1") (class "Default")
      (node (ref "J12") (pin "3") (pinfunction "3_3") (pintype "passive"))
      (node (ref "J3") (pin "5") (pinfunction "5_5") (pintype "passive"))
    )
    (net (code "82") (name "/~{RST}") (class "Default")
      (node (ref "J7") (pin "1") (pinfunction "1_1") (pintype "passive"))
      (node (ref "R2") (pin "1") (pinfunction "1_1") (pintype "passive"))
      (node (ref "R3") (pin "2") (pinfunction "2_2") (pintype "passive"))
      (node (ref "R4") (pin "1") (pinfunction "1_1") (pintype "passive"))
    )
    (net (code "83") (name "3.3V") (class "Default")
      (node (ref "C1") (pin "A") (pinfunction "+_A") (pintype "passive"))
      (node (ref "J15") (pin "1") (pinfunction "1_1") (pintype "passive"))
      (node (ref "J15") (pin "3") (pinfunction "3_3") (pintype "passive"))
      (node (ref "J3") (pin "1") (pinfunction "1_1") (pintype "passive"))
      (node (ref "U1") (pin "3") (pinfunction "OUT_3") (pintype "bidirectional"))
      (node (ref "U9") (pin "2") (pinfunction "VR1_2") (pintype "bidirectional"))
    )
    (net (code "84") (name "GND") (class "Default")
      (node (ref "C1") (pin "C") (pinfunction "-_C") (pintype "passive"))
      (node (ref "C10") (pin "1") (pinfunction "1_1") (pintype "passive"))
      (node (ref "C11") (pin "1") (pinfunction "1_1") (pintype "passive"))
      (node (ref "C12") (pin "2") (pinfunction "2_2") (pintype "passive"))
      (node (ref "C13") (pin "2") (pinfunction "2_2") (pintype "passive"))
      (node (ref "C14") (pin "2") (pinfunction "2_2") (pintype "passive"))
      (node (ref "C15") (pin "-") (pinfunction "-_-") (pintype "passive"))
      (node (ref "C16") (pin "2") (pinfunction "2_2") (pintype "passive"))
      (node (ref "C17") (pin "-") (pinfunction "-_-") (pintype "passive"))
      (node (ref "C18") (pin "2") (pinfunction "2_2") (pintype "passive"))
      (node (ref "C19") (pin "1") (pinfunction "1_1") (pintype "passive"))
      (node (ref "C2") (pin "2") (pinfunction "-_2") (pintype "passive"))
      (node (ref "C23") (pin "2") (pinfunction "2_2") (pintype "passive"))
      (node (ref "C24") (pin "2") (pinfunction "-_2") (pintype "passive"))
      (node (ref "C25") (pin "2") (pinfunction "2_2") (pintype "passive"))
      (node (ref "C27") (pin "1") (pinfunction "1_1") (pintype "passive"))
      (node (ref "C3") (pin "1") (pinfunction "1_1") (pintype "passive"))
      (node (ref "C4") (pin "-") (pinfunction "-_-") (pintype "passive"))
      (node (ref "C5") (pin "-") (pinfunction "-_-") (pintype "passive"))
      (node (ref "C6") (pin "-") (pinfunction "-_-") (pintype "passive"))
      (node (ref "C7") (pin "2") (pinfunction "2_2") (pintype "passive"))
      (node (ref "C8") (pin "-") (pinfunction "-_-") (pintype "passive"))
      (node (ref "C9") (pin "2") (pinfunction "2_2") (pintype "passive"))
      (node (ref "D1") (pin "A") (pinfunction "A_A") (pintype "passive"))
      (node (ref "J11") (pin "5") (pinfunction "5_5") (pintype "passive"))
      (node (ref "J12") (pin "2") (pinfunction "2_2") (pintype "passive"))
      (node (ref "J13") (pin "3") (pinfunction "3_3") (pintype "passive"))
      (node (ref "J14") (pin "2") (pinfunction "2_2") (pintype "passive"))
      (node (ref "J15") (pin "2") (pinfunction "2_2") (pintype "passive"))
      (node (ref "J15") (pin "4") (pinfunction "4_4") (pintype "passive"))
      (node (ref "J16") (pin "3") (pinfunction "3_3") (pintype "passive"))
      (node (ref "J20") (pin "1") (pinfunction "1_1") (pintype "passive"))
      (node (ref "J20") (pin "10") (pinfunction "10_10") (pintype "passive"))
      (node (ref "J20") (pin "13") (pinfunction "13_13") (pintype "passive"))
      (node (ref "J20") (pin "16") (pinfunction "16_16") (pintype "passive"))
      (node (ref "J20") (pin "19") (pinfunction "19_19") (pintype "passive"))
      (node (ref "J20") (pin "22") (pinfunction "22_22") (pintype "passive"))
      (node (ref "J20") (pin "25") (pinfunction "25_25") (pintype "passive"))
      (node (ref "J20") (pin "28") (pinfunction "28_28") (pintype "passive"))
      (node (ref "J20") (pin "31") (pinfunction "31_31") (pintype "passive"))
      (node (ref "J20") (pin "34") (pinfunction "34_34") (pintype "passive"))
      (node (ref "J20") (pin "37") (pinfunction "37_37") (pintype "passive"))
      (node (ref "J20") (pin "4") (pinfunction "4_4") (pintype "passive"))
      (node (ref "J20") (pin "40") (pinfunction "40_40") (pintype "passive"))
      (node (ref "J20") (pin "43") (pinfunction "43_43") (pintype "passive"))
      (node (ref "J20") (pin "46") (pinfunction "46_46") (pintype "passive"))
      (node (ref "J20") (pin "49") (pinfunction "49_49") (pintype "passive"))
      (node (ref "J20") (pin "7") (pinfunction "7_7") (pintype "passive"))
      (node (ref "J3") (pin "16") (pinfunction "16_16") (pintype "passive"))
      (node (ref "J3") (pin "2") (pinfunction "2_2") (pintype "passive"))
      (node (ref "J4") (pin "5") (pinfunction "5_5") (pintype "passive"))
      (node (ref "J5") (pin "2") (pinfunction "2_2") (pintype "passive"))
      (node (ref "J6") (pin "12") (pinfunction "12_12") (pintype "passive"))
      (node (ref "J6") (pin "15") (pinfunction "15_15") (pintype "passive"))
      (node (ref "J6") (pin "18") (pinfunction "18_18") (pintype "passive"))
      (node (ref "J6") (pin "21") (pinfunction "21_21") (pintype "passive"))
      (node (ref "J6") (pin "24") (pinfunction "24_24") (pintype "passive"))
      (node (ref "J6") (pin "27") (pinfunction "27_27") (pintype "passive"))
      (node (ref "J6") (pin "3") (pinfunction "3_3") (pintype "passive"))
      (node (ref "J6") (pin "30") (pinfunction "30_30") (pintype "passive"))
      (node (ref "J6") (pin "33") (pinfunction "33_33") (pintype "passive"))
      (node (ref "J6") (pin "36") (pinfunction "36_36") (pintype "passive"))
      (node (ref "J6") (pin "39") (pinfunction "39_39") (pintype "passive"))
      (node (ref "J6") (pin "42") (pinfunction "42_42") (pintype "passive"))
      (node (ref "J6") (pin "45") (pinfunction "45_45") (pintype "passive"))
      (node (ref "J6") (pin "48") (pinfunction "48_48") (pintype "passive"))
      (node (ref "J6") (pin "51") (pinfunction "51_51") (pintype "passive"))
      (node (ref "J6") (pin "6") (pinfunction "6_6") (pintype "passive"))
      (node (ref "J6") (pin "9") (pinfunction "9_9") (pintype "passive"))
      (node (ref "J7") (pin "3") (pinfunction "3_3") (pintype "passive"))
      (node (ref "J8") (pin "10") (pinfunction "10_10") (pintype "passive"))
      (node (ref "R23") (pin "1") (pinfunction "1_1") (pintype "passive"))
      (node (ref "U1") (pin "2") (pinfunction "GND_2") (pintype "bidirectional"))
      (node (ref "U11") (pin "1") (pinfunction "GND_1") (pintype "bidirectional"))
      (node (ref "U14") (pin "20") (pinfunction "AVSS_20") (pintype "power_in"))
      (node (ref "U14") (pin "25") (pinfunction "VSS_25") (pintype "power_in"))
      (node (ref "U14") (pin "41") (pinfunction "VSS_41") (pintype "power_in"))
      (node (ref "U14") (pin "56") (pinfunction "VSS_56") (pintype "power_in"))
      (node (ref "U14") (pin "9") (pinfunction "VSS_9") (pintype "power_in"))
      (node (ref "U15") (pin "10") (pinfunction "GND_10") (pintype "power_in"))
      (node (ref "U15") (pin "2") (pinfunction "RTRY_2") (pintype "input"))
      (node (ref "U15") (pin "8") (pinfunction "LSS_8") (pintype "output"))
      (node (ref "U15") (pin "PAD") (pinfunction "PAD_PAD") (pintype "output"))
      (node (ref "U2") (pin "3") (pinfunction "GND_3") (pintype "bidirectional"))
      (node (ref "U2") (pin "5") (pinfunction "SD_5") (pintype "bidirectional"))
      (node (ref "U2") (pin "6") (pinfunction "GND_6") (pintype "bidirectional"))
      (node (ref "U3") (pin "10") (pinfunction "GND_10") (pintype "power_in"))
      (node (ref "U3") (pin "2") (pinfunction "RTRY_2") (pintype "input"))
      (node (ref "U3") (pin "8") (pinfunction "LSS_8") (pintype "output"))
      (node (ref "U3") (pin "PAD") (pinfunction "PAD_PAD") (pintype "output"))
      (node (ref "U4") (pin "10") (pinfunction "GND_10") (pintype "power_in"))
      (node (ref "U4") (pin "2") (pinfunction "RTRY_2") (pintype "input"))
      (node (ref "U4") (pin "8") (pinfunction "LSS_8") (pintype "output"))
      (node (ref "U4") (pin "PAD") (pinfunction "PAD_PAD") (pintype "output"))
      (node (ref "U5") (pin "10") (pinfunction "GND_10") (pintype "power_in"))
      (node (ref "U5") (pin "2") (pinfunction "RTRY_2") (pintype "input"))
      (node (ref "U5") (pin "8") (pinfunction "LSS_8") (pintype "output"))
      (node (ref "U5") (pin "PAD") (pinfunction "PAD_PAD") (pintype "output"))
      (node (ref "U9") (pin "1") (pinfunction "GND_1") (pintype "bidirectional"))
    )
    (net (code "85") (name "Net-(C19-Pad2)") (class "Default")
      (node (ref "C19") (pin "2") (pinfunction "2_2") (pintype "passive"))
      (node (ref "R4") (pin "2") (pinfunction "2_2") (pintype "passive"))
    )
    (net (code "86") (name "Net-(D2-A)") (class "Default")
      (node (ref "D2") (pin "2") (pinfunction "A_2") (pintype "passive"))
      (node (ref "J5") (pin "1") (pinfunction "1_1") (pintype "passive"))
    )
    (net (code "87") (name "Net-(D4-A)") (class "Default")
      (node (ref "D4") (pin "2") (pinfunction "A_2") (pintype "passive"))
      (node (ref "J20") (pin "14") (pinfunction "14_14") (pintype "passive"))
    )
    (net (code "88") (name "Net-(D4-C)") (class "Default")
      (node (ref "D4") (pin "1") (pinfunction "C_1") (pintype "passive"))
      (node (ref "J20") (pin "11") (pinfunction "11_11") (pintype "passive"))
      (node (ref "J20") (pin "2") (pinfunction "2_2") (pintype "passive"))
      (node (ref "J20") (pin "5") (pinfunction "5_5") (pintype "passive"))
      (node (ref "J20") (pin "8") (pinfunction "8_8") (pintype "passive"))
    )
    (net (code "89") (name "Net-(D6-A)") (class "Default")
      (node (ref "D6") (pin "2") (pinfunction "A_2") (pintype "passive"))
      (node (ref "J6") (pin "14") (pinfunction "14_14") (pintype "passive"))
    )
    (net (code "90") (name "Net-(D6-C)") (class "Default")
      (node (ref "D6") (pin "1") (pinfunction "C_1") (pintype "passive"))
      (node (ref "J6") (pin "11") (pinfunction "11_11") (pintype "passive"))
      (node (ref "J6") (pin "2") (pinfunction "2_2") (pintype "passive"))
      (node (ref "J6") (pin "5") (pinfunction "5_5") (pintype "passive"))
      (node (ref "J6") (pin "8") (pinfunction "8_8") (pintype "passive"))
    )
    (net (code "91") (name "Net-(LED1-PadC)") (class "Default")
      (node (ref "LED1") (pin "C") (pinfunction "C_C") (pintype "passive"))
      (node (ref "R19") (pin "1") (pinfunction "1_1") (pintype "passive"))
    )
    (net (code "92") (name "Net-(U2-FB)") (class "Default")
      (node (ref "R22") (pin "1") (pinfunction "1_1") (pintype "passive"))
      (node (ref "R23") (pin "2") (pinfunction "2_2") (pintype "passive"))
      (node (ref "U2") (pin "4") (pinfunction "FB_4") (pintype "bidirectional"))
    )
    (net (code "93") (name "Net-(U2-OUT)") (class "Default")
      (node (ref "D1") (pin "C") (pinfunction "C_C") (pintype "passive"))
      (node (ref "L1") (pin "1") (pinfunction "1_1") (pintype "passive"))
      (node (ref "U2") (pin "2") (pinfunction "OUT_2") (pintype "bidirectional"))
    )
    (net (code "94") (name "Net-(U3-OUT1)") (class "Default")
      (node (ref "J2") (pin "3") (pinfunction "3_3") (pintype "passive"))
      (node (ref "U3") (pin "7") (pinfunction "OUT1_7") (pintype "output"))
    )
    (net (code "95") (name "Net-(U3-OUT2)") (class "Default")
      (node (ref "J2") (pin "4") (pinfunction "4_4") (pintype "passive"))
      (node (ref "U3") (pin "9") (pinfunction "OUT2_9") (pintype "input"))
    )
    (net (code "96") (name "Net-(U4-OUT1)") (class "Default")
      (node (ref "J1") (pin "2") (pinfunction "2_2") (pintype "passive"))
      (node (ref "U4") (pin "7") (pinfunction "OUT1_7") (pintype "output"))
    )
    (net (code "97") (name "Net-(U4-OUT2)") (class "Default")
      (node (ref "J1") (pin "1") (pinfunction "1_1") (pintype "passive"))
      (node (ref "U4") (pin "9") (pinfunction "OUT2_9") (pintype "input"))
    )
    (net (code "98") (name "Net-(U5-OUT1)") (class "Default")
      (node (ref "J1") (pin "4") (pinfunction "4_4") (pintype "passive"))
      (node (ref "U5") (pin "7") (pinfunction "OUT1_7") (pintype "output"))
    )
    (net (code "99") (name "Net-(U5-OUT2)") (class "Default")
      (node (ref "J1") (pin "3") (pinfunction "3_3") (pintype "passive"))
      (node (ref "U5") (pin "9") (pinfunction "OUT2_9") (pintype "input"))
    )
    (net (code "100") (name "Net-(U9-EN)") (class "Default")
      (node (ref "C27") (pin "2") (pinfunction "2_2") (pintype "passive"))
      (node (ref "R32") (pin "1") (pinfunction "1_1") (pintype "passive"))
      (node (ref "U9") (pin "7") (pinfunction "VR2_7") (pintype "bidirectional"))
      (node (ref "U9") (pin "8") (pinfunction "EN_8") (pintype "input"))
    )
    (net (code "101") (name "Net-(U14-AVDD)") (class "Default")
      (node (ref "C9") (pin "1") (pinfunction "1_1") (pintype "passive"))
      (node (ref "R1") (pin "2") (pinfunction "2_2") (pintype "passive"))
      (node (ref "U14") (pin "19") (pinfunction "AVDD_19") (pintype "power_in"))
    )
    (net (code "102") (name "Net-(U14-VDDCORE{slash}VCAP)") (class "Default")
      (node (ref "C3") (pin "2") (pinfunction "2_2") (pintype "passive"))
      (node (ref "U14") (pin "10") (pinfunction "VDDCORE/VCAP_10") (pintype "power_in"))
    )
    (net (code "103") (name "Net-(U14-~{MCLR{slash}}RG5)") (class "Default")
      (node (ref "R3") (pin "1") (pinfunction "1_1") (pintype "passive"))
      (node (ref "U14") (pin "7") (pinfunction "~{MCLR/}RG5_7") (pintype "input"))
    )
    (net (code "104") (name "Net-(U15-OUT1)") (class "Default")
      (node (ref "J2") (pin "1") (pinfunction "1_1") (pintype "passive"))
      (node (ref "U15") (pin "7") (pinfunction "OUT1_7") (pintype "output"))
    )
    (net (code "105") (name "Net-(U15-OUT2)") (class "Default")
      (node (ref "J2") (pin "2") (pinfunction "2_2") (pintype "passive"))
      (node (ref "U15") (pin "9") (pinfunction "OUT2_9") (pintype "input"))
    )
    (net (code "106") (name "unconnected-(J12-Pad1)") (class "Default")
      (node (ref "J12") (pin "1") (pinfunction "1_1") (pintype "passive"))
    )
    (net (code "107") (name "unconnected-(J14-Pad1)") (class "Default")
      (node (ref "J14") (pin "1") (pinfunction "1_1") (pintype "passive"))
    )
    (net (code "108") (name "unconnected-(U$1-1-PadP$2)") (class "Default")
      (node (ref "U$1") (pin "P$2") (pinfunction "1_P$2") (pintype "bidirectional"))
    )
    (net (code "109") (name "unconnected-(U$2-1-PadP$2)") (class "Default")
      (node (ref "U$2") (pin "P$2") (pinfunction "1_P$2") (pintype "bidirectional"))
    )
    (net (code "110") (name "unconnected-(U$7-1-PadP$2)") (class "Default")
      (node (ref "U$7") (pin "P$2") (pinfunction "1_P$2") (pintype "bidirectional"))
    )
    (net (code "111") (name "unconnected-(U$8-1-PadP$2)") (class "Default")
      (node (ref "U$8") (pin "P$2") (pinfunction "1_P$2") (pintype "bidirectional"))
    )
    (net (code "112") (name "unconnected-(U3-FAULT-Pad1)") (class "Default")
      (node (ref "U3") (pin "1") (pinfunction "FAULT_1") (pintype "output"))
    )
    (net (code "113") (name "unconnected-(U4-FAULT-Pad1)") (class "Default")
      (node (ref "U4") (pin "1") (pinfunction "FAULT_1") (pintype "output"))
    )
    (net (code "114") (name "unconnected-(U5-FAULT-Pad1)") (class "Default")
      (node (ref "U5") (pin "1") (pinfunction "FAULT_1") (pintype "output"))
    )
    (net (code "115") (name "unconnected-(U14-RE0{slash}~{RD{slash}}P2D-Pad2)") (class "Default")
      (node (ref "U14") (pin "2") (pinfunction "RE0/~{RD/}P2D_2") (pintype "bidirectional"))
    )
    (net (code "116") (name "unconnected-(U14-RE1{slash}~{WR{slash}}P2C-Pad1)") (class "Default")
      (node (ref "U14") (pin "1") (pinfunction "RE1/~{WR/}P2C_1") (pintype "bidirectional"))
    )
    (net (code "117") (name "unconnected-(U14-RG0{slash}ECCP3{slash}P3A-Pad3)") (class "Default")
      (node (ref "U14") (pin "3") (pinfunction "RG0/ECCP3/P3A_3") (pintype "bidirectional"))
    )
    (net (code "118") (name "unconnected-(U15-FAULT-Pad1)") (class "Default")
      (node (ref "U15") (pin "1") (pinfunction "FAULT_1") (pintype "output"))
    )
  )
)
